# PWM_Signal_Amplifiers.net
KiCad netlist of a schematic drawn in Altium Designer
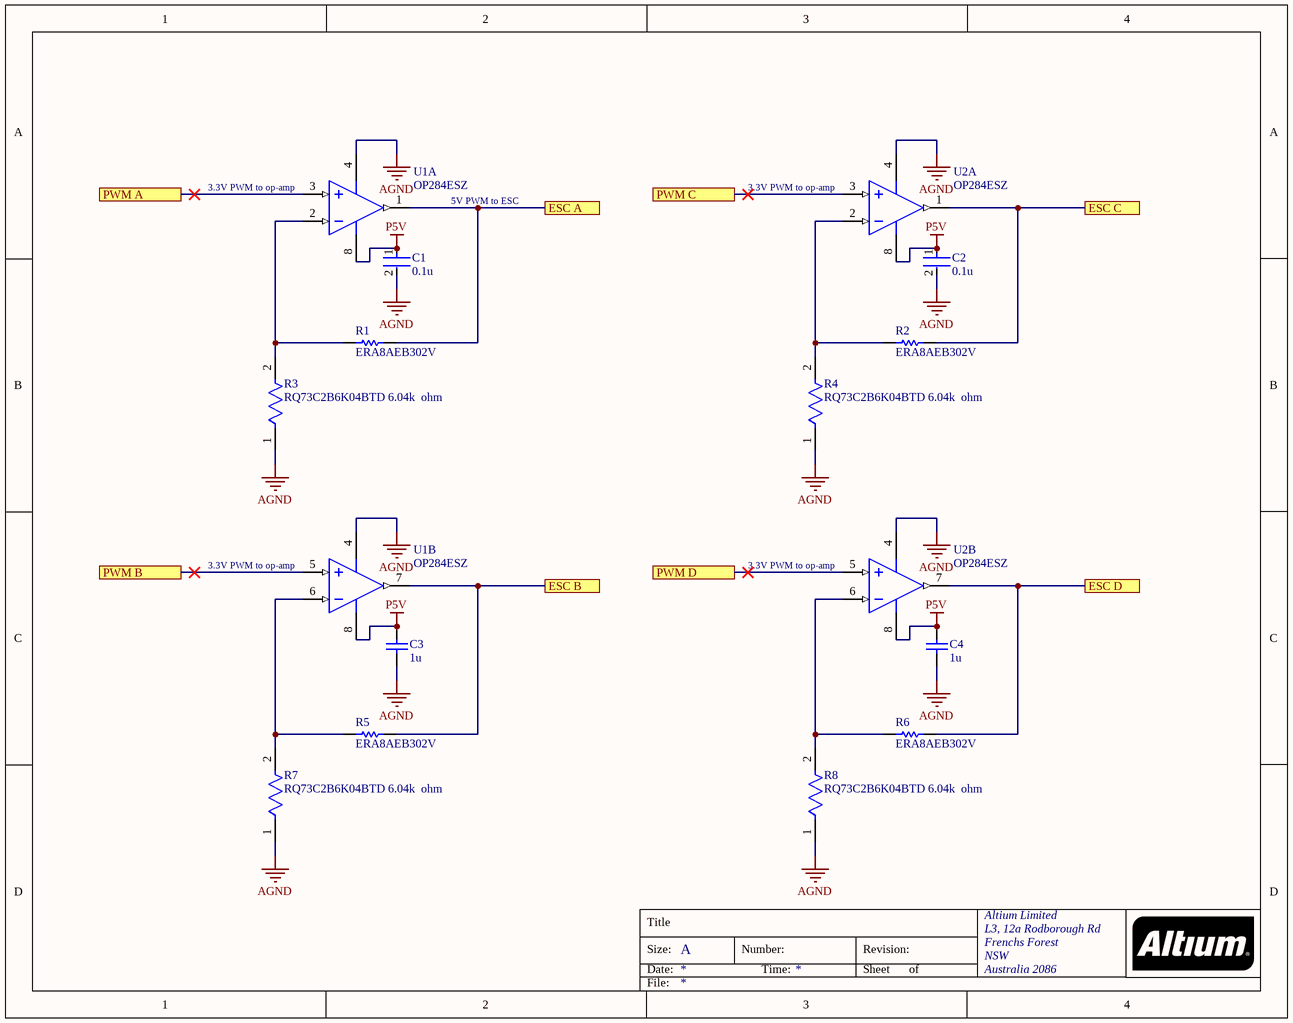
[diagram p0: PWM_Signal_Amplifiers.SchDoc]

(export (version "E")
  (design (tool "Eeschema 10.0.6"))
  (components
    (comp (ref "C1")
      (value "0.1u")
      (footprint "FP-C0402-BB-MFG")
      (description "CAP CER 0.1UF 10V X5R 0402")
      (fields (field (name "MANUFACTURER") "Kemet") (field (name "TOLERANCE") "0.1"))
      (libsource (lib "Altium Content Vault") (part "b4654b650e69147ec39a6b967a45e02"))
    )
    (comp (ref "C2")
      (value "0.1u")
      (footprint "FP-C0402-BB-MFG")
      (description "CAP CER 0.1UF 10V X5R 0402")
      (fields (field (name "MANUFACTURER") "Kemet") (field (name "TOLERANCE") "0.1"))
      (libsource (lib "Altium Content Vault") (part "b4654b650e69147ec39a6b967a45e02"))
    )
    (comp (ref "C3")
      (value "1u")
      (footprint "CAPC3216X110X50LL20T25")
      (description "Chip Capacitor, 1 uF, +/- 10%, 50 V, -55 to 125 degC, 1206 (3216 Metric), RoHS, Tape and Reel")
      (fields (field (name "MANUFACTURER") "Kemet") (field (name "TOLERANCE") "10%"))
      (libsource (lib "Altium Content Vault") (part "CAP-NP-2"))
    )
    (comp (ref "C4")
      (value "1u")
      (footprint "CAPC3216X110X50LL20T25")
      (description "Chip Capacitor, 1 uF, +/- 10%, 50 V, -55 to 125 degC, 1206 (3216 Metric), RoHS, Tape and Reel")
      (fields (field (name "MANUFACTURER") "Kemet") (field (name "TOLERANCE") "10%"))
      (libsource (lib "Altium Content Vault") (part "CAP-NP-2"))
    )
    (comp (ref "R1")
      (value "ERA8AEB302V")
      (footprint "RESC3216X70X50ML20T25")
      (fields (field (name "MANUFACTURER") "Panasonic"))
      (libsource (lib "Altium Content Vault") (part "RES"))
    )
    (comp (ref "R2")
      (value "ERA8AEB302V")
      (footprint "RESC3216X70X50ML20T25")
      (fields (field (name "MANUFACTURER") "Panasonic"))
      (libsource (lib "Altium Content Vault") (part "RES"))
    )
    (comp (ref "R3")
      (value "RQ73C2B6K04BTD 6.04k  ohm")
      (footprint "FP-RQ732B-IPC_C")
      (description "RQ732B 1206 6.04KΩ 0.4W 10ppm/°C 0.1% 200V")
      (fields (field (name "MANUFACTURER") "TE") (field (name "TOLERANCE") "0.1%"))
      (libsource (lib "Altium Content Vault") (part "1029c3af85768c4190bb7ad29bc67b5"))
    )
    (comp (ref "R4")
      (value "RQ73C2B6K04BTD 6.04k  ohm")
      (footprint "FP-RQ732B-IPC_C")
      (description "RQ732B 1206 6.04KΩ 0.4W 10ppm/°C 0.1% 200V")
      (fields (field (name "MANUFACTURER") "TE") (field (name "TOLERANCE") "0.1%"))
      (libsource (lib "Altium Content Vault") (part "1029c3af85768c4190bb7ad29bc67b5"))
    )
    (comp (ref "R5")
      (value "ERA8AEB302V")
      (footprint "RESC3216X70X50ML20T25")
      (fields (field (name "MANUFACTURER") "Panasonic"))
      (libsource (lib "Altium Content Vault") (part "RES"))
    )
    (comp (ref "R6")
      (value "ERA8AEB302V")
      (footprint "RESC3216X70X50ML20T25")
      (fields (field (name "MANUFACTURER") "Panasonic"))
      (libsource (lib "Altium Content Vault") (part "RES"))
    )
    (comp (ref "R7")
      (value "RQ73C2B6K04BTD 6.04k  ohm")
      (footprint "FP-RQ732B-IPC_C")
      (description "RQ732B 1206 6.04KΩ 0.4W 10ppm/°C 0.1% 200V")
      (fields (field (name "MANUFACTURER") "TE") (field (name "TOLERANCE") "0.1%"))
      (libsource (lib "Altium Content Vault") (part "1029c3af85768c4190bb7ad29bc67b5"))
    )
    (comp (ref "R8")
      (value "RQ73C2B6K04BTD 6.04k  ohm")
      (footprint "FP-RQ732B-IPC_C")
      (description "RQ732B 1206 6.04KΩ 0.4W 10ppm/°C 0.1% 200V")
      (fields (field (name "MANUFACTURER") "TE") (field (name "TOLERANCE") "0.1%"))
      (libsource (lib "Altium Content Vault") (part "1029c3af85768c4190bb7ad29bc67b5"))
    )
    (comp (ref "U1")
      (value "OP284ESZ")
      (footprint "ADI-R-8_L")
      (fields (field (name "GENERIC PART NUMBER") "OP284") (field (name "MANUFACTURER") "Analog Devices"))
      (libsource (lib "Altium Content Vault") (part "ADI-OP29X-R-8"))
    )
    (comp (ref "U2")
      (value "OP284ESZ")
      (footprint "ADI-R-8_L")
      (fields (field (name "GENERIC PART NUMBER") "OP284") (field (name "MANUFACTURER") "Analog Devices"))
      (libsource (lib "Altium Content Vault") (part "ADI-OP29X-R-8"))
    )
  )
  (nets
    (net (code "1") (name "/ESC A") (class "Default")
      (node (ref "R1") (pin "2") (pinfunction "2_2") (pintype "passive"))
      (node (ref "U1") (pin "1") (pinfunction "OUT_A_1") (pintype "output"))
    )
    (net (code "2") (name "/ESC B") (class "Default")
      (node (ref "R5") (pin "2") (pinfunction "2_2") (pintype "passive"))
      (node (ref "U1") (pin "7") (pinfunction "OUT_B_7") (pintype "output"))
    )
    (net (code "3") (name "/ESC C") (class "Default")
      (node (ref "R2") (pin "2") (pinfunction "2_2") (pintype "passive"))
      (node (ref "U2") (pin "1") (pinfunction "OUT_A_1") (pintype "output"))
    )
    (net (code "4") (name "/ESC D") (class "Default")
      (node (ref "R6") (pin "2") (pinfunction "2_2") (pintype "passive"))
      (node (ref "U2") (pin "7") (pinfunction "OUT_B_7") (pintype "output"))
    )
    (net (code "5") (name "/PWM A") (class "Default")
      (node (ref "U1") (pin "3") (pinfunction "+IN_A_3") (pintype "input"))
    )
    (net (code "6") (name "/PWM B") (class "Default")
      (node (ref "U1") (pin "5") (pinfunction "+IN_B_5") (pintype "input"))
    )
    (net (code "7") (name "/PWM C") (class "Default")
      (node (ref "U2") (pin "3") (pinfunction "+IN_A_3") (pintype "input"))
    )
    (net (code "8") (name "/PWM D") (class "Default")
      (node (ref "U2") (pin "5") (pinfunction "+IN_B_5") (pintype "input"))
    )
    (net (code "9") (name "AGND") (class "Default")
      (node (ref "C1") (pin "2") (pinfunction "2_2") (pintype "passive"))
      (node (ref "C2") (pin "2") (pinfunction "2_2") (pintype "passive"))
      (node (ref "C3") (pin "1") (pinfunction "1_1") (pintype "passive"))
      (node (ref "C4") (pin "1") (pinfunction "1_1") (pintype "passive"))
      (node (ref "R3") (pin "1") (pinfunction "1_1") (pintype "passive"))
      (node (ref "R4") (pin "1") (pinfunction "1_1") (pintype "passive"))
      (node (ref "R7") (pin "1") (pinfunction "1_1") (pintype "passive"))
      (node (ref "R8") (pin "1") (pinfunction "1_1") (pintype "passive"))
      (node (ref "U1") (pin "4") (pinfunction "-V_4") (pintype "power_in"))
      (node (ref "U2") (pin "4") (pinfunction "-V_4") (pintype "power_in"))
    )
    (net (code "10") (name "Net-(U1A--IN_A)") (class "Default")
      (node (ref "R1") (pin "1") (pinfunction "1_1") (pintype "passive"))
      (node (ref "R3") (pin "2") (pinfunction "2_2") (pintype "passive"))
      (node (ref "U1") (pin "2") (pinfunction "-IN_A_2") (pintype "input"))
    )
    (net (code "11") (name "Net-(U1B--IN_B)") (class "Default")
      (node (ref "R5") (pin "1") (pinfunction "1_1") (pintype "passive"))
      (node (ref "R7") (pin "2") (pinfunction "2_2") (pintype "passive"))
      (node (ref "U1") (pin "6") (pinfunction "-IN_B_6") (pintype "input"))
    )
    (net (code "12") (name "Net-(U2A--IN_A)") (class "Default")
      (node (ref "R2") (pin "1") (pinfunction "1_1") (pintype "passive"))
      (node (ref "R4") (pin "2") (pinfunction "2_2") (pintype "passive"))
      (node (ref "U2") (pin "2") (pinfunction "-IN_A_2") (pintype "input"))
    )
    (net (code "13") (name "Net-(U2B--IN_B)") (class "Default")
      (node (ref "R6") (pin "1") (pinfunction "1_1") (pintype "passive"))
      (node (ref "R8") (pin "2") (pinfunction "2_2") (pintype "passive"))
      (node (ref "U2") (pin "6") (pinfunction "-IN_B_6") (pintype "input"))
    )
    (net (code "14") (name "P5V") (class "Default")
      (node (ref "C1") (pin "1") (pinfunction "1_1") (pintype "passive"))
      (node (ref "C2") (pin "1") (pinfunction "1_1") (pintype "passive"))
      (node (ref "C3") (pin "2") (pinfunction "2_2") (pintype "passive"))
      (node (ref "C4") (pin "2") (pinfunction "2_2") (pintype "passive"))
      (node (ref "U1") (pin "8") (pinfunction "+V_8") (pintype "power_in"))
      (node (ref "U2") (pin "8") (pinfunction "+V_8") (pintype "power_in"))
    )
  )
)
